# Klok.net
KiCad netlist of a schematic drawn in Altium Designer
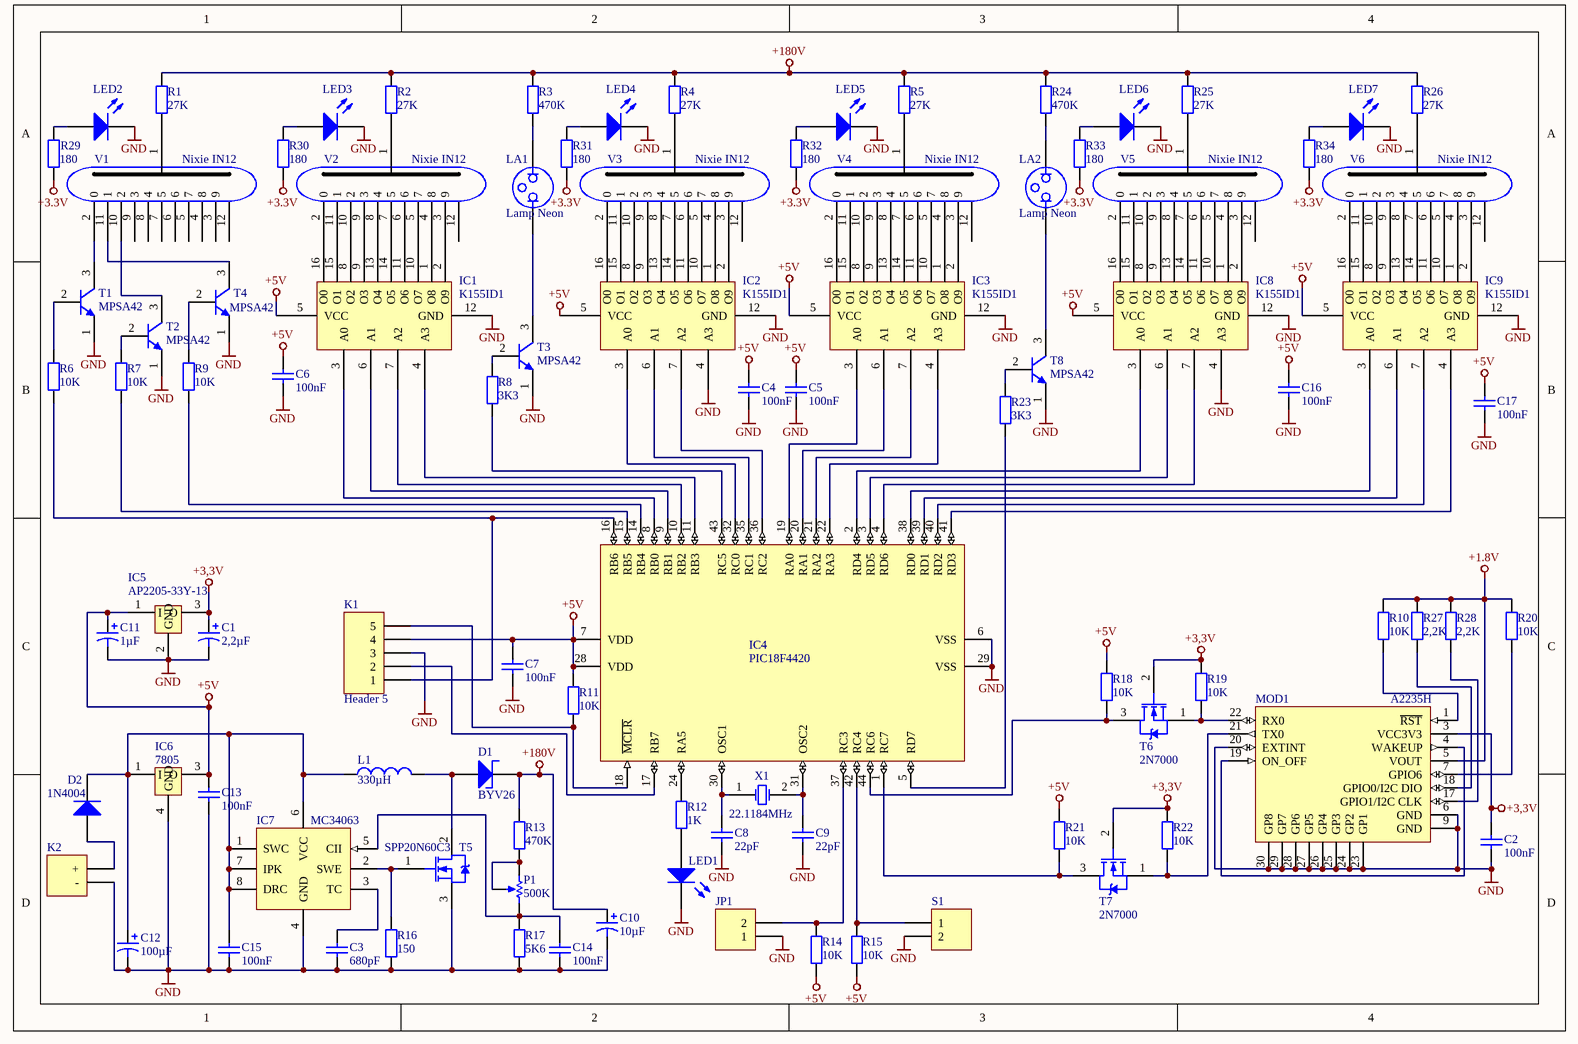
[diagram p0: Klok.SchDoc]

(export (version "E")
  (design (tool "Eeschema 10.0.6"))
  (components
    (comp (ref "C1")
      (value "2,2µF")
      (footprint "ELCO2.2")
      (description "Polarized Capacitor (Radial)")
      (fields (field (name "Comment") "Cap Pol1") (field (name "PUBLISHER") "Altium Limited"))
      (libsource (lib "Miscellaneous Devices") (part "Cap Pol1"))
    )
    (comp (ref "C2")
      (value "100nF")
      (footprint "1206_Capacitor")
      (description "Capacitor")
      (fields (field (name "Comment") "Cap") (field (name "PUBLISHER") "Altium Limited"))
      (libsource (lib "Miscellaneous Devices") (part "Cap"))
    )
    (comp (ref "C3")
      (value "680pF")
      (footprint "1206_Capacitor")
      (description "Capacitor")
      (fields (field (name "Comment") "Cap") (field (name "PUBLISHER") "Altium Limited"))
      (libsource (lib "Miscellaneous Devices") (part "Cap"))
    )
    (comp (ref "C4")
      (value "100nF")
      (footprint "1206_Capacitor")
      (description "Capacitor")
      (fields (field (name "Comment") "Cap") (field (name "PUBLISHER") "Altium Limited"))
      (libsource (lib "Miscellaneous Devices") (part "Cap"))
    )
    (comp (ref "C5")
      (value "100nF")
      (footprint "1206_Capacitor")
      (description "Capacitor")
      (fields (field (name "Comment") "Cap") (field (name "PUBLISHER") "Altium Limited"))
      (libsource (lib "Miscellaneous Devices") (part "Cap"))
    )
    (comp (ref "C6")
      (value "100nF")
      (footprint "1206_Capacitor")
      (description "Capacitor")
      (fields (field (name "Comment") "Cap") (field (name "PUBLISHER") "Altium Limited"))
      (libsource (lib "Miscellaneous Devices") (part "Cap"))
    )
    (comp (ref "C7")
      (value "100nF")
      (footprint "1206_Capacitor")
      (description "Capacitor")
      (fields (field (name "Comment") "Cap") (field (name "PUBLISHER") "Altium Limited"))
      (libsource (lib "Miscellaneous Devices") (part "Cap"))
    )
    (comp (ref "C8")
      (value "22pF")
      (footprint "1206_Capacitor")
      (description "Capacitor")
      (fields (field (name "Comment") "Cap") (field (name "PUBLISHER") "Altium Limited"))
      (libsource (lib "Miscellaneous Devices") (part "Cap"))
    )
    (comp (ref "C9")
      (value "22pF")
      (footprint "1206_Capacitor")
      (description "Capacitor")
      (fields (field (name "Comment") "Cap") (field (name "PUBLISHER") "Altium Limited"))
      (libsource (lib "Miscellaneous Devices") (part "Cap"))
    )
    (comp (ref "C10")
      (value "10µF")
      (footprint "ELCO10")
      (description "Polarized Capacitor (Radial)")
      (fields (field (name "Comment") "Cap Pol1") (field (name "PUBLISHER") "Altium Limited"))
      (libsource (lib "Miscellaneous Devices") (part "Cap Pol1"))
    )
    (comp (ref "C11")
      (value "1µF")
      (footprint "ELCO100")
      (description "Polarized Capacitor (Radial)")
      (fields (field (name "Comment") "Cap Pol1") (field (name "PUBLISHER") "Altium Limited"))
      (libsource (lib "Miscellaneous Devices") (part "Cap Pol1"))
    )
    (comp (ref "C12")
      (value "100µF")
      (footprint "ELCO100")
      (description "Polarized Capacitor (Radial)")
      (fields (field (name "Comment") "Cap Pol1") (field (name "PUBLISHER") "Altium Limited"))
      (libsource (lib "Miscellaneous Devices") (part "Cap Pol1"))
    )
    (comp (ref "C13")
      (value "100nF")
      (footprint "1206_Capacitor")
      (description "Capacitor")
      (fields (field (name "Comment") "Cap") (field (name "PUBLISHER") "Altium Limited"))
      (libsource (lib "Miscellaneous Devices") (part "Cap"))
    )
    (comp (ref "C14")
      (value "100nF")
      (footprint "1206_Capacitor")
      (description "Capacitor")
      (fields (field (name "Comment") "Cap") (field (name "PUBLISHER") "Altium Limited"))
      (libsource (lib "Miscellaneous Devices") (part "Cap"))
    )
    (comp (ref "C15")
      (value "100nF")
      (footprint "1206_Capacitor")
      (description "Capacitor")
      (fields (field (name "Comment") "Cap") (field (name "PUBLISHER") "Altium Limited"))
      (libsource (lib "Miscellaneous Devices") (part "Cap"))
    )
    (comp (ref "C16")
      (value "100nF")
      (footprint "1206_Capacitor")
      (description "Capacitor")
      (fields (field (name "Comment") "Cap") (field (name "PUBLISHER") "Altium Limited"))
      (libsource (lib "Miscellaneous Devices") (part "Cap"))
    )
    (comp (ref "C17")
      (value "100nF")
      (footprint "1206_Capacitor")
      (description "Capacitor")
      (fields (field (name "Comment") "Cap") (field (name "PUBLISHER") "Altium Limited"))
      (libsource (lib "Miscellaneous Devices") (part "Cap"))
    )
    (comp (ref "D1") (value "BYV26") (footprint "Through_Hole") (libsource (lib "Klok") (part "BYV26")))
    (comp (ref "D2")
      (value "1N4004")
      (footprint "DO-41")
      (description "1 Amp General Purpose Rectifier")
      (fields (field (name "PUBLISHER") "Altium Limited"))
      (libsource (lib "Miscellaneous Devices") (part "Diode 1N4004"))
    )
    (comp (ref "IC1") (value "K155ID1") (footprint "K155ID1") (libsource (lib "Klok") (part "K155ID1")))
    (comp (ref "IC2") (value "K155ID1") (footprint "K155ID1") (libsource (lib "Klok") (part "K155ID1")))
    (comp (ref "IC3") (value "K155ID1") (footprint "K155ID1") (libsource (lib "Klok") (part "K155ID1")))
    (comp (ref "IC4")
      (value "PIC18F4420")
      (footprint "PIC18F4420")
      (libsource (lib "Klok") (part "PIC18F4420"))
    )
    (comp (ref "IC5")
      (value "AP2205-33Y-13")
      (footprint "AP2205-33Y-13")
      (libsource (lib "Klok") (part "AP2205-33Y-13"))
    )
    (comp (ref "IC6") (value "7805") (footprint "7805") (libsource (lib "Klok") (part "7805")))
    (comp (ref "IC7") (value "MC34063") (footprint "MC34063") (libsource (lib "Klok") (part "MC34063")))
    (comp (ref "IC8") (value "K155ID1") (footprint "K155ID1") (libsource (lib "Klok") (part "K155ID1")))
    (comp (ref "IC9") (value "K155ID1") (footprint "K155ID1") (libsource (lib "Klok") (part "K155ID1")))
    (comp (ref "JP1")
      (value "Header 2")
      (footprint "HDR1X2")
      (description "Header, 2-Pin")
      (fields (field (name "PUBLISHER") "Altium Limited"))
      (libsource (lib "Miscellaneous Connectors") (part "Header 2"))
    )
    (comp (ref "K1")
      (value "Header 5")
      (footprint "HDR1X5")
      (description "Header, 5-Pin")
      (fields (field (name "PUBLISHER") "Altium Limited"))
      (libsource (lib "Miscellaneous Connectors") (part "Header 5"))
    )
    (comp (ref "K2")
      (value "Kroonsteen")
      (footprint "KROONSTEEN")
      (description "Header, 2-Pin")
      (fields (field (name "PUBLISHER") "Altium Limited"))
      (libsource (lib "") (part "Header 2_1"))
    )
    (comp (ref "L1")
      (value "330µH")
      (footprint "Inductor")
      (description "Inductor")
      (fields (field (name "PUBLISHER") "Altium Limited"))
      (libsource (lib "Miscellaneous Devices") (part "Inductor"))
    )
    (comp (ref "LA1")
      (value "Lamp Neon")
      (footprint "Neon_Lamp")
      (description "Neon Lamp")
      (fields (field (name "PUBLISHER") "Altium Limited"))
      (libsource (lib "Miscellaneous Devices") (part "Lamp Neon"))
    )
    (comp (ref "LA2")
      (value "Lamp Neon")
      (footprint "Neon_Lamp")
      (description "Neon Lamp")
      (fields (field (name "PUBLISHER") "Altium Limited"))
      (libsource (lib "Miscellaneous Devices") (part "Lamp Neon"))
    )
    (comp (ref "LED1")
      (value "LED0")
      (footprint "1206_LED")
      (description "Typical INFRARED GaAs LED")
      (fields (field (name "PUBLISHER") "Altium Limited"))
      (libsource (lib "Miscellaneous Devices") (part "LED0"))
    )
    (comp (ref "LED2")
      (value "LED0")
      (footprint "1206_LED")
      (description "Typical INFRARED GaAs LED")
      (fields (field (name "PUBLISHER") "Altium Limited"))
      (libsource (lib "Miscellaneous Devices") (part "LED0"))
    )
    (comp (ref "LED3")
      (value "LED0")
      (footprint "1206_LED")
      (description "Typical INFRARED GaAs LED")
      (fields (field (name "PUBLISHER") "Altium Limited"))
      (libsource (lib "Miscellaneous Devices") (part "LED0"))
    )
    (comp (ref "LED4")
      (value "LED0")
      (footprint "1206_LED")
      (description "Typical INFRARED GaAs LED")
      (fields (field (name "PUBLISHER") "Altium Limited"))
      (libsource (lib "Miscellaneous Devices") (part "LED0"))
    )
    (comp (ref "LED5")
      (value "LED0")
      (footprint "1206_LED")
      (description "Typical INFRARED GaAs LED")
      (fields (field (name "PUBLISHER") "Altium Limited"))
      (libsource (lib "Miscellaneous Devices") (part "LED0"))
    )
    (comp (ref "LED6")
      (value "LED0")
      (footprint "1206_LED")
      (description "Typical INFRARED GaAs LED")
      (fields (field (name "PUBLISHER") "Altium Limited"))
      (libsource (lib "Miscellaneous Devices") (part "LED0"))
    )
    (comp (ref "LED7")
      (value "LED0")
      (footprint "1206_LED")
      (description "Typical INFRARED GaAs LED")
      (fields (field (name "PUBLISHER") "Altium Limited"))
      (libsource (lib "Miscellaneous Devices") (part "LED0"))
    )
    (comp (ref "MOD1") (value "A2235H") (footprint "A2235H") (libsource (lib "Klok") (part "A2235H")))
    (comp (ref "P1")
      (value "500K")
      (footprint "Pot")
      (description "Potentiometer")
      (fields (field (name "Comment") "RPot") (field (name "PUBLISHER") "Altium Limited"))
      (libsource (lib "Miscellaneous Devices") (part "RPot"))
    )
    (comp (ref "R1")
      (value "27K")
      (footprint "1206_Resistor")
      (description "Resistor")
      (fields (field (name "Comment") "Res2") (field (name "PUBLISHER") "Altium Limited"))
      (libsource (lib "Miscellaneous Devices") (part "Res2"))
    )
    (comp (ref "R2")
      (value "27K")
      (footprint "1206_Resistor")
      (description "Resistor")
      (fields (field (name "Comment") "Res2") (field (name "PUBLISHER") "Altium Limited"))
      (libsource (lib "Miscellaneous Devices") (part "Res2"))
    )
    (comp (ref "R3")
      (value "470K")
      (footprint "1206_Resistor")
      (description "Resistor")
      (fields (field (name "Comment") "Res2") (field (name "PUBLISHER") "Altium Limited"))
      (libsource (lib "Miscellaneous Devices") (part "Res2"))
    )
    (comp (ref "R4")
      (value "27K")
      (footprint "1206_Resistor")
      (description "Resistor")
      (fields (field (name "Comment") "Res2") (field (name "PUBLISHER") "Altium Limited"))
      (libsource (lib "Miscellaneous Devices") (part "Res2"))
    )
    (comp (ref "R5")
      (value "27K")
      (footprint "1206_Resistor")
      (description "Resistor")
      (fields (field (name "Comment") "Res2") (field (name "PUBLISHER") "Altium Limited"))
      (libsource (lib "Miscellaneous Devices") (part "Res2"))
    )
    (comp (ref "R6")
      (value "10K")
      (footprint "1206_Resistor")
      (description "Resistor")
      (fields (field (name "Comment") "Res2") (field (name "PUBLISHER") "Altium Limited"))
      (libsource (lib "Miscellaneous Devices") (part "Res2"))
    )
    (comp (ref "R7")
      (value "10K")
      (footprint "1206_Resistor")
      (description "Resistor")
      (fields (field (name "Comment") "Res2") (field (name "PUBLISHER") "Altium Limited"))
      (libsource (lib "Miscellaneous Devices") (part "Res2"))
    )
    (comp (ref "R8")
      (value "3K3")
      (footprint "1206_Resistor")
      (description "Resistor")
      (fields (field (name "Comment") "Res2") (field (name "PUBLISHER") "Altium Limited"))
      (libsource (lib "Miscellaneous Devices") (part "Res2"))
    )
    (comp (ref "R9")
      (value "10K")
      (footprint "1206_Resistor")
      (description "Resistor")
      (fields (field (name "Comment") "Res2") (field (name "PUBLISHER") "Altium Limited"))
      (libsource (lib "Miscellaneous Devices") (part "Res2"))
    )
    (comp (ref "R10")
      (value "10K")
      (footprint "1206_Resistor")
      (description "Resistor")
      (fields (field (name "Comment") "Res2") (field (name "PUBLISHER") "Altium Limited"))
      (libsource (lib "Miscellaneous Devices") (part "Res2"))
    )
    (comp (ref "R11")
      (value "10K")
      (footprint "1206_Resistor")
      (description "Resistor")
      (fields (field (name "Comment") "Res2") (field (name "PUBLISHER") "Altium Limited"))
      (libsource (lib "Miscellaneous Devices") (part "Res2"))
    )
    (comp (ref "R12")
      (value "1K")
      (footprint "1206_Resistor")
      (description "Resistor")
      (fields (field (name "Comment") "Res2") (field (name "PUBLISHER") "Altium Limited"))
      (libsource (lib "Miscellaneous Devices") (part "Res2"))
    )
    (comp (ref "R13")
      (value "470K")
      (footprint "1206_Resistor")
      (description "Resistor")
      (fields (field (name "Comment") "Res2") (field (name "PUBLISHER") "Altium Limited"))
      (libsource (lib "Miscellaneous Devices") (part "Res2"))
    )
    (comp (ref "R14")
      (value "10K")
      (footprint "1206_Resistor")
      (description "Resistor")
      (fields (field (name "Comment") "Res2") (field (name "PUBLISHER") "Altium Limited"))
      (libsource (lib "Miscellaneous Devices") (part "Res2"))
    )
    (comp (ref "R15")
      (value "10K")
      (footprint "1206_Resistor")
      (description "Resistor")
      (fields (field (name "Comment") "Res2") (field (name "PUBLISHER") "Altium Limited"))
      (libsource (lib "Miscellaneous Devices") (part "Res2"))
    )
    (comp (ref "R16")
      (value "150")
      (footprint "1206_Resistor")
      (description "Resistor")
      (fields (field (name "Comment") "Res2") (field (name "PUBLISHER") "Altium Limited"))
      (libsource (lib "Miscellaneous Devices") (part "Res2"))
    )
    (comp (ref "R17")
      (value "5K6")
      (footprint "1206_Resistor")
      (description "Resistor")
      (fields (field (name "Comment") "Res2") (field (name "PUBLISHER") "Altium Limited"))
      (libsource (lib "Miscellaneous Devices") (part "Res2"))
    )
    (comp (ref "R18")
      (value "10K")
      (footprint "1206_Resistor")
      (description "Resistor")
      (fields (field (name "Comment") "Res2") (field (name "PUBLISHER") "Altium Limited"))
      (libsource (lib "Miscellaneous Devices") (part "Res2"))
    )
    (comp (ref "R19")
      (value "10K")
      (footprint "1206_Resistor")
      (description "Resistor")
      (fields (field (name "Comment") "Res2") (field (name "PUBLISHER") "Altium Limited"))
      (libsource (lib "Miscellaneous Devices") (part "Res2"))
    )
    (comp (ref "R20")
      (value "10K")
      (footprint "1206_Resistor")
      (description "Resistor")
      (fields (field (name "Comment") "Res2") (field (name "PUBLISHER") "Altium Limited"))
      (libsource (lib "Miscellaneous Devices") (part "Res2"))
    )
    (comp (ref "R21")
      (value "10K")
      (footprint "1206_Resistor")
      (description "Resistor")
      (fields (field (name "Comment") "Res2") (field (name "PUBLISHER") "Altium Limited"))
      (libsource (lib "Miscellaneous Devices") (part "Res2"))
    )
    (comp (ref "R22")
      (value "10K")
      (footprint "1206_Resistor")
      (description "Resistor")
      (fields (field (name "Comment") "Res2") (field (name "PUBLISHER") "Altium Limited"))
      (libsource (lib "Miscellaneous Devices") (part "Res2"))
    )
    (comp (ref "R23")
      (value "3K3")
      (footprint "1206_Resistor")
      (description "Resistor")
      (fields (field (name "Comment") "Res2") (field (name "PUBLISHER") "Altium Limited"))
      (libsource (lib "Miscellaneous Devices") (part "Res2"))
    )
    (comp (ref "R24")
      (value "470K")
      (footprint "1206_Resistor")
      (description "Resistor")
      (fields (field (name "Comment") "Res2") (field (name "PUBLISHER") "Altium Limited"))
      (libsource (lib "Miscellaneous Devices") (part "Res2"))
    )
    (comp (ref "R25")
      (value "27K")
      (footprint "1206_Resistor")
      (description "Resistor")
      (fields (field (name "Comment") "Res2") (field (name "PUBLISHER") "Altium Limited"))
      (libsource (lib "Miscellaneous Devices") (part "Res2"))
    )
    (comp (ref "R26")
      (value "27K")
      (footprint "1206_Resistor")
      (description "Resistor")
      (fields (field (name "Comment") "Res2") (field (name "PUBLISHER") "Altium Limited"))
      (libsource (lib "Miscellaneous Devices") (part "Res2"))
    )
    (comp (ref "R27")
      (value "2,2K")
      (footprint "1206_Resistor")
      (description "Resistor")
      (fields (field (name "Comment") "Res2") (field (name "PUBLISHER") "Altium Limited"))
      (libsource (lib "Miscellaneous Devices") (part "Res2"))
    )
    (comp (ref "R28")
      (value "2,2K")
      (footprint "1206_Resistor")
      (description "Resistor")
      (fields (field (name "Comment") "Res2") (field (name "PUBLISHER") "Altium Limited"))
      (libsource (lib "Miscellaneous Devices") (part "Res2"))
    )
    (comp (ref "R29")
      (value "180")
      (footprint "1206_Resistor")
      (description "Resistor")
      (fields (field (name "Comment") "Res2") (field (name "PUBLISHER") "Altium Limited"))
      (libsource (lib "Miscellaneous Devices") (part "Res2"))
    )
    (comp (ref "R30")
      (value "180")
      (footprint "1206_Resistor")
      (description "Resistor")
      (fields (field (name "Comment") "Res2") (field (name "PUBLISHER") "Altium Limited"))
      (libsource (lib "Miscellaneous Devices") (part "Res2"))
    )
    (comp (ref "R31")
      (value "180")
      (footprint "1206_Resistor")
      (description "Resistor")
      (fields (field (name "Comment") "Res2") (field (name "PUBLISHER") "Altium Limited"))
      (libsource (lib "Miscellaneous Devices") (part "Res2"))
    )
    (comp (ref "R32")
      (value "180")
      (footprint "1206_Resistor")
      (description "Resistor")
      (fields (field (name "Comment") "Res2") (field (name "PUBLISHER") "Altium Limited"))
      (libsource (lib "Miscellaneous Devices") (part "Res2"))
    )
    (comp (ref "R33")
      (value "180")
      (footprint "1206_Resistor")
      (description "Resistor")
      (fields (field (name "Comment") "Res2") (field (name "PUBLISHER") "Altium Limited"))
      (libsource (lib "Miscellaneous Devices") (part "Res2"))
    )
    (comp (ref "R34")
      (value "180")
      (footprint "1206_Resistor")
      (description "Resistor")
      (fields (field (name "Comment") "Res2") (field (name "PUBLISHER") "Altium Limited"))
      (libsource (lib "Miscellaneous Devices") (part "Res2"))
    )
    (comp (ref "S1")
      (value "Switch")
      (footprint "HDR1X2")
      (description "Header, 2-Pin")
      (fields (field (name "PUBLISHER") "Altium Limited"))
      (libsource (lib "") (part "Header 2_2"))
    )
    (comp (ref "T1") (value "MPSA42") (footprint "MPSA42") (libsource (lib "Klok") (part "MPSA42")))
    (comp (ref "T2") (value "MPSA42") (footprint "MPSA42") (libsource (lib "Klok") (part "MPSA42")))
    (comp (ref "T3") (value "MPSA42") (footprint "MPSA42") (libsource (lib "Klok") (part "MPSA42")))
    (comp (ref "T4") (value "MPSA42") (footprint "MPSA42") (libsource (lib "Klok") (part "MPSA42")))
    (comp (ref "T5")
      (value "SPP20N60C3")
      (footprint "SPP20N60C3")
      (libsource (lib "Klok") (part "SPP20N60C3"))
    )
    (comp (ref "T6") (value "2N7000") (footprint "2N7000") (libsource (lib "Klok") (part "2N7000")))
    (comp (ref "T7") (value "2N7000") (footprint "2N7000") (libsource (lib "Klok") (part "2N7000")))
    (comp (ref "T8") (value "MPSA42") (footprint "MPSA42") (libsource (lib "Klok") (part "MPSA42")))
    (comp (ref "V1")
      (value "Nixie IN12")
      (footprint "Nixie IN12")
      (libsource (lib "Klok") (part "Nixie IN12"))
    )
    (comp (ref "V2")
      (value "Nixie IN12")
      (footprint "Nixie IN12")
      (libsource (lib "Klok") (part "Nixie IN12"))
    )
    (comp (ref "V3")
      (value "Nixie IN12")
      (footprint "Nixie IN12")
      (libsource (lib "Klok") (part "Nixie IN12"))
    )
    (comp (ref "V4")
      (value "Nixie IN12")
      (footprint "Nixie IN12")
      (libsource (lib "Klok") (part "Nixie IN12"))
    )
    (comp (ref "V5")
      (value "Nixie IN12")
      (footprint "Nixie IN12")
      (libsource (lib "Klok") (part "Nixie IN12"))
    )
    (comp (ref "V6")
      (value "Nixie IN12")
      (footprint "Nixie IN12")
      (libsource (lib "Klok") (part "Nixie IN12"))
    )
    (comp (ref "X1")
      (value "22.1184MHz")
      (footprint "XTAL - duplicate")
      (description "Crystal Oscillator")
      (fields (field (name "PUBLISHER") "Altium Limited"))
      (libsource (lib "Miscellaneous Devices") (part "XTAL"))
    )
  )
  (nets
    (net (code "1") (name "+1.8V") (class "Default")
      (node (ref "MOD1") (pin "5") (pinfunction "VOUT_5") (pintype "power_in"))
      (node (ref "R10") (pin "2") (pinfunction "2_2") (pintype "passive"))
      (node (ref "R20") (pin "2") (pinfunction "2_2") (pintype "passive"))
      (node (ref "R27") (pin "2") (pinfunction "2_2") (pintype "passive"))
      (node (ref "R28") (pin "2") (pinfunction "2_2") (pintype "passive"))
    )
    (net (code "2") (name "+3,3V") (class "Default")
      (node (ref "C1") (pin "1") (pinfunction "1_1") (pintype "passive"))
      (node (ref "C2") (pin "2") (pinfunction "2_2") (pintype "passive"))
      (node (ref "IC5") (pin "3") (pinfunction "O_3") (pintype "power_in"))
      (node (ref "MOD1") (pin "3") (pinfunction "VCC3V3_3") (pintype "power_in"))
      (node (ref "R19") (pin "2") (pinfunction "2_2") (pintype "passive"))
      (node (ref "R22") (pin "2") (pinfunction "2_2") (pintype "passive"))
      (node (ref "T6") (pin "2") (pinfunction "G_2") (pintype "passive"))
      (node (ref "T7") (pin "2") (pinfunction "G_2") (pintype "passive"))
    )
    (net (code "3") (name "+3.3V") (class "Default")
      (node (ref "R29") (pin "1") (pinfunction "1_1") (pintype "passive"))
      (node (ref "R30") (pin "1") (pinfunction "1_1") (pintype "passive"))
      (node (ref "R31") (pin "1") (pinfunction "1_1") (pintype "passive"))
      (node (ref "R32") (pin "1") (pinfunction "1_1") (pintype "passive"))
      (node (ref "R33") (pin "1") (pinfunction "1_1") (pintype "passive"))
      (node (ref "R34") (pin "1") (pinfunction "1_1") (pintype "passive"))
    )
    (net (code "4") (name "+5V") (class "Default")
      (node (ref "C11") (pin "1") (pinfunction "1_1") (pintype "passive"))
      (node (ref "C13") (pin "2") (pinfunction "2_2") (pintype "passive"))
      (node (ref "C16") (pin "2") (pinfunction "2_2") (pintype "passive"))
      (node (ref "C17") (pin "2") (pinfunction "2_2") (pintype "passive"))
      (node (ref "C4") (pin "2") (pinfunction "2_2") (pintype "passive"))
      (node (ref "C5") (pin "2") (pinfunction "2_2") (pintype "passive"))
      (node (ref "C6") (pin "2") (pinfunction "2_2") (pintype "passive"))
      (node (ref "C7") (pin "2") (pinfunction "2_2") (pintype "passive"))
      (node (ref "IC1") (pin "5") (pinfunction "VCC_5") (pintype "passive"))
      (node (ref "IC2") (pin "5") (pinfunction "VCC_5") (pintype "passive"))
      (node (ref "IC3") (pin "5") (pinfunction "VCC_5") (pintype "passive"))
      (node (ref "IC4") (pin "28") (pinfunction "VDD_28") (pintype "power_in"))
      (node (ref "IC4") (pin "7") (pinfunction "VDD_7") (pintype "power_in"))
      (node (ref "IC5") (pin "1") (pinfunction "I_1") (pintype "power_in"))
      (node (ref "IC6") (pin "3") (pinfunction "O_3") (pintype "power_in"))
      (node (ref "IC8") (pin "5") (pinfunction "VCC_5") (pintype "passive"))
      (node (ref "IC9") (pin "5") (pinfunction "VCC_5") (pintype "passive"))
      (node (ref "K1") (pin "4") (pinfunction "4_4") (pintype "passive"))
      (node (ref "R11") (pin "2") (pinfunction "2_2") (pintype "passive"))
      (node (ref "R14") (pin "1") (pinfunction "1_1") (pintype "passive"))
      (node (ref "R15") (pin "1") (pinfunction "1_1") (pintype "passive"))
      (node (ref "R18") (pin "2") (pinfunction "2_2") (pintype "passive"))
      (node (ref "R21") (pin "2") (pinfunction "2_2") (pintype "passive"))
    )
    (net (code "5") (name "+180V") (class "Default")
      (node (ref "C10") (pin "1") (pinfunction "1_1") (pintype "passive"))
      (node (ref "D1") (pin "2") (pinfunction "K_2") (pintype "passive"))
      (node (ref "R1") (pin "2") (pinfunction "2_2") (pintype "passive"))
      (node (ref "R13") (pin "2") (pinfunction "2_2") (pintype "passive"))
      (node (ref "R2") (pin "2") (pinfunction "2_2") (pintype "passive"))
      (node (ref "R24") (pin "2") (pinfunction "2_2") (pintype "passive"))
      (node (ref "R25") (pin "2") (pinfunction "2_2") (pintype "passive"))
      (node (ref "R26") (pin "2") (pinfunction "2_2") (pintype "passive"))
      (node (ref "R3") (pin "2") (pinfunction "2_2") (pintype "passive"))
      (node (ref "R4") (pin "2") (pinfunction "2_2") (pintype "passive"))
      (node (ref "R5") (pin "2") (pinfunction "2_2") (pintype "passive"))
    )
    (net (code "6") (name "GND") (class "Default")
      (node (ref "C1") (pin "2") (pinfunction "2_2") (pintype "passive"))
      (node (ref "C10") (pin "2") (pinfunction "2_2") (pintype "passive"))
      (node (ref "C11") (pin "2") (pinfunction "2_2") (pintype "passive"))
      (node (ref "C12") (pin "2") (pinfunction "2_2") (pintype "passive"))
      (node (ref "C13") (pin "1") (pinfunction "1_1") (pintype "passive"))
      (node (ref "C14") (pin "1") (pinfunction "1_1") (pintype "passive"))
      (node (ref "C15") (pin "1") (pinfunction "1_1") (pintype "passive"))
      (node (ref "C16") (pin "1") (pinfunction "1_1") (pintype "passive"))
      (node (ref "C17") (pin "1") (pinfunction "1_1") (pintype "passive"))
      (node (ref "C2") (pin "1") (pinfunction "1_1") (pintype "passive"))
      (node (ref "C3") (pin "1") (pinfunction "1_1") (pintype "passive"))
      (node (ref "C4") (pin "1") (pinfunction "1_1") (pintype "passive"))
      (node (ref "C5") (pin "1") (pinfunction "1_1") (pintype "passive"))
      (node (ref "C6") (pin "1") (pinfunction "1_1") (pintype "passive"))
      (node (ref "C7") (pin "1") (pinfunction "1_1") (pintype "passive"))
      (node (ref "C8") (pin "1") (pinfunction "1_1") (pintype "passive"))
      (node (ref "C9") (pin "1") (pinfunction "1_1") (pintype "passive"))
      (node (ref "IC1") (pin "12") (pinfunction "GND_12") (pintype "passive"))
      (node (ref "IC2") (pin "12") (pinfunction "GND_12") (pintype "passive"))
      (node (ref "IC2") (pin "4") (pinfunction "A3_4") (pintype "passive"))
      (node (ref "IC3") (pin "12") (pinfunction "GND_12") (pintype "passive"))
      (node (ref "IC4") (pin "29") (pinfunction "VSS_29") (pintype "power_in"))
      (node (ref "IC4") (pin "6") (pinfunction "VSS_6") (pintype "power_in"))
      (node (ref "IC5") (pin "2") (pinfunction "GND_2") (pintype "power_in"))
      (node (ref "IC6") (pin "4") (pinfunction "GND_4") (pintype "power_in"))
      (node (ref "IC7") (pin "4") (pinfunction "GND_4") (pintype "power_in"))
      (node (ref "IC8") (pin "12") (pinfunction "GND_12") (pintype "passive"))
      (node (ref "IC8") (pin "4") (pinfunction "A3_4") (pintype "passive"))
      (node (ref "IC9") (pin "12") (pinfunction "GND_12") (pintype "passive"))
      (node (ref "JP1") (pin "1") (pinfunction "1_1") (pintype "passive"))
      (node (ref "K1") (pin "3") (pinfunction "3_3") (pintype "passive"))
      (node (ref "K2") (pin "1") (pinfunction "-_1") (pintype "passive"))
      (node (ref "LED1") (pin "2") (pinfunction "K_2") (pintype "passive"))
      (node (ref "LED2") (pin "2") (pinfunction "K_2") (pintype "passive"))
      (node (ref "LED3") (pin "2") (pinfunction "K_2") (pintype "passive"))
      (node (ref "LED4") (pin "2") (pinfunction "K_2") (pintype "passive"))
      (node (ref "LED5") (pin "2") (pinfunction "K_2") (pintype "passive"))
      (node (ref "LED6") (pin "2") (pinfunction "K_2") (pintype "passive"))
      (node (ref "LED7") (pin "2") (pinfunction "K_2") (pintype "passive"))
      (node (ref "MOD1") (pin "20") (pinfunction "EXTINT_20") (pintype "bidirectional"))
      (node (ref "MOD1") (pin "23") (pinfunction "GP1_23") (pintype "power_in"))
      (node (ref "MOD1") (pin "24") (pinfunction "GP2_24") (pintype "power_in"))
      (node (ref "MOD1") (pin "25") (pinfunction "GP3_25") (pintype "power_in"))
      (node (ref "MOD1") (pin "26") (pinfunction "GP4_26") (pintype "power_in"))
      (node (ref "MOD1") (pin "27") (pinfunction "GP5_27") (pintype "power_in"))
      (node (ref "MOD1") (pin "28") (pinfunction "GP6_28") (pintype "power_in"))
      (node (ref "MOD1") (pin "29") (pinfunction "GP7_29") (pintype "power_in"))
      (node (ref "MOD1") (pin "30") (pinfunction "GP8_30") (pintype "power_in"))
      (node (ref "MOD1") (pin "6") (pinfunction "GND_6") (pintype "power_in"))
      (node (ref "MOD1") (pin "9") (pinfunction "GND_9") (pintype "power_in"))
      (node (ref "R16") (pin "1") (pinfunction "1_1") (pintype "passive"))
      (node (ref "R17") (pin "1") (pinfunction "1_1") (pintype "passive"))
      (node (ref "S1") (pin "2") (pinfunction "2_2") (pintype "passive"))
      (node (ref "T1") (pin "1") (pinfunction "E_1") (pintype "passive"))
      (node (ref "T2") (pin "1") (pinfunction "E_1") (pintype "passive"))
      (node (ref "T3") (pin "1") (pinfunction "E_1") (pintype "passive"))
      (node (ref "T4") (pin "1") (pinfunction "E_1") (pintype "passive"))
      (node (ref "T5") (pin "3") (pinfunction "SOURCE_3") (pintype "passive"))
      (node (ref "T8") (pin "1") (pinfunction "E_1") (pintype "passive"))
    )
    (net (code "7") (name "Net-(D1-A)") (class "Default")
      (node (ref "D1") (pin "1") (pinfunction "A_1") (pintype "passive"))
      (node (ref "L1") (pin "2") (pinfunction "2_2") (pintype "passive"))
      (node (ref "T5") (pin "2") (pinfunction "DRAIN_2") (pintype "passive"))
    )
    (net (code "8") (name "Net-(D2-A)") (class "Default")
      (node (ref "D2") (pin "1") (pinfunction "A_1") (pintype "passive"))
      (node (ref "K2") (pin "2") (pinfunction "+_2") (pintype "passive"))
    )
    (net (code "9") (name "Net-(D2-K)") (class "Default")
      (node (ref "C12") (pin "1") (pinfunction "1_1") (pintype "passive"))
      (node (ref "C15") (pin "2") (pinfunction "2_2") (pintype "passive"))
      (node (ref "D2") (pin "2") (pinfunction "K_2") (pintype "passive"))
      (node (ref "IC6") (pin "1") (pinfunction "I_1") (pintype "power_in"))
      (node (ref "IC7") (pin "1") (pinfunction "SWC_1") (pintype "open_collector"))
      (node (ref "IC7") (pin "6") (pinfunction "VCC_6") (pintype "power_in"))
      (node (ref "IC7") (pin "7") (pinfunction "IPK_7") (pintype "passive"))
      (node (ref "IC7") (pin "8") (pinfunction "DRC_8") (pintype "open_collector"))
      (node (ref "L1") (pin "1") (pinfunction "1_1") (pintype "passive"))
    )
    (net (code "10") (name "Net-(IC1-A0)") (class "Default")
      (node (ref "IC1") (pin "3") (pinfunction "A0_3") (pintype "passive"))
      (node (ref "IC4") (pin "8") (pinfunction "RB0_8") (pintype "bidirectional"))
    )
    (net (code "11") (name "Net-(IC1-A1)") (class "Default")
      (node (ref "IC1") (pin "6") (pinfunction "A1_6") (pintype "passive"))
      (node (ref "IC4") (pin "9") (pinfunction "RB1_9") (pintype "bidirectional"))
    )
    (net (code "12") (name "Net-(IC1-A2)") (class "Default")
      (node (ref "IC1") (pin "7") (pinfunction "A2_7") (pintype "passive"))
      (node (ref "IC4") (pin "10") (pinfunction "RB2_10") (pintype "bidirectional"))
    )
    (net (code "13") (name "Net-(IC1-A3)") (class "Default")
      (node (ref "IC1") (pin "4") (pinfunction "A3_4") (pintype "passive"))
      (node (ref "IC4") (pin "11") (pinfunction "RB3_11") (pintype "bidirectional"))
    )
    (net (code "14") (name "Net-(IC1-O0)") (class "Default")
      (node (ref "IC1") (pin "16") (pinfunction "O0_16") (pintype "passive"))
      (node (ref "V2") (pin "2") (pinfunction "0_2") (pintype "passive"))
    )
    (net (code "15") (name "Net-(IC1-O1)") (class "Default")
      (node (ref "IC1") (pin "15") (pinfunction "O1_15") (pintype "passive"))
      (node (ref "V2") (pin "11") (pinfunction "1_11") (pintype "passive"))
    )
    (net (code "16") (name "Net-(IC1-O2)") (class "Default")
      (node (ref "IC1") (pin "8") (pinfunction "O2_8") (pintype "passive"))
      (node (ref "V2") (pin "10") (pinfunction "2_10") (pintype "passive"))
    )
    (net (code "17") (name "Net-(IC1-O3)") (class "Default")
      (node (ref "IC1") (pin "9") (pinfunction "O3_9") (pintype "passive"))
      (node (ref "V2") (pin "9") (pinfunction "3_9") (pintype "passive"))
    )
    (net (code "18") (name "Net-(IC1-O4)") (class "Default")
      (node (ref "IC1") (pin "13") (pinfunction "O4_13") (pintype "passive"))
      (node (ref "V2") (pin "8") (pinfunction "4_8") (pintype "passive"))
    )
    (net (code "19") (name "Net-(IC1-O5)") (class "Default")
      (node (ref "IC1") (pin "14") (pinfunction "O5_14") (pintype "passive"))
      (node (ref "V2") (pin "7") (pinfunction "5_7") (pintype "passive"))
    )
    (net (code "20") (name "Net-(IC1-O6)") (class "Default")
      (node (ref "IC1") (pin "11") (pinfunction "O6_11") (pintype "passive"))
      (node (ref "V2") (pin "6") (pinfunction "6_6") (pintype "passive"))
    )
    (net (code "21") (name "Net-(IC1-O7)") (class "Default")
      (node (ref "IC1") (pin "10") (pinfunction "O7_10") (pintype "passive"))
      (node (ref "V2") (pin "5") (pinfunction "7_5") (pintype "passive"))
    )
    (net (code "22") (name "Net-(IC1-O8)") (class "Default")
      (node (ref "IC1") (pin "1") (pinfunction "O8_1") (pintype "passive"))
      (node (ref "V2") (pin "4") (pinfunction "8_4") (pintype "passive"))
    )
    (net (code "23") (name "Net-(IC1-O9)") (class "Default")
      (node (ref "IC1") (pin "2") (pinfunction "O9_2") (pintype "passive"))
      (node (ref "V2") (pin "3") (pinfunction "9_3") (pintype "passive"))
    )
    (net (code "24") (name "Net-(IC2-A0)") (class "Default")
      (node (ref "IC2") (pin "3") (pinfunction "A0_3") (pintype "passive"))
      (node (ref "IC4") (pin "32") (pinfunction "RC0_32") (pintype "bidirectional"))
    )
    (net (code "25") (name "Net-(IC2-A1)") (class "Default")
      (node (ref "IC2") (pin "6") (pinfunction "A1_6") (pintype "passive"))
      (node (ref "IC4") (pin "35") (pinfunction "RC1_35") (pintype "bidirectional"))
    )
    (net (code "26") (name "Net-(IC2-A2)") (class "Default")
      (node (ref "IC2") (pin "7") (pinfunction "A2_7") (pintype "passive"))
      (node (ref "IC4") (pin "36") (pinfunction "RC2_36") (pintype "bidirectional"))
    )
    (net (code "27") (name "Net-(IC2-O0)") (class "Default")
      (node (ref "IC2") (pin "16") (pinfunction "O0_16") (pintype "passive"))
      (node (ref "V3") (pin "2") (pinfunction "0_2") (pintype "passive"))
    )
    (net (code "28") (name "Net-(IC2-O1)") (class "Default")
      (node (ref "IC2") (pin "15") (pinfunction "O1_15") (pintype "passive"))
      (node (ref "V3") (pin "11") (pinfunction "1_11") (pintype "passive"))
    )
    (net (code "29") (name "Net-(IC2-O2)") (class "Default")
      (node (ref "IC2") (pin "8") (pinfunction "O2_8") (pintype "passive"))
      (node (ref "V3") (pin "10") (pinfunction "2_10") (pintype "passive"))
    )
    (net (code "30") (name "Net-(IC2-O3)") (class "Default")
      (node (ref "IC2") (pin "9") (pinfunction "O3_9") (pintype "passive"))
      (node (ref "V3") (pin "9") (pinfunction "3_9") (pintype "passive"))
    )
    (net (code "31") (name "Net-(IC2-O4)") (class "Default")
      (node (ref "IC2") (pin "13") (pinfunction "O4_13") (pintype "passive"))
      (node (ref "V3") (pin "8") (pinfunction "4_8") (pintype "passive"))
    )
    (net (code "32") (name "Net-(IC2-O5)") (class "Default")
      (node (ref "IC2") (pin "14") (pinfunction "O5_14") (pintype "passive"))
      (node (ref "V3") (pin "7") (pinfunction "5_7") (pintype "passive"))
    )
    (net (code "33") (name "Net-(IC2-O6)") (class "Default")
      (node (ref "IC2") (pin "11") (pinfunction "O6_11") (pintype "passive"))
      (node (ref "V3") (pin "6") (pinfunction "6_6") (pintype "passive"))
    )
    (net (code "34") (name "Net-(IC2-O7)") (class "Default")
      (node (ref "IC2") (pin "10") (pinfunction "O7_10") (pintype "passive"))
      (node (ref "V3") (pin "5") (pinfunction "7_5") (pintype "passive"))
    )
    (net (code "35") (name "Net-(IC2-O8)") (class "Default")
      (node (ref "IC2") (pin "1") (pinfunction "O8_1") (pintype "passive"))
      (node (ref "V3") (pin "4") (pinfunction "8_4") (pintype "passive"))
    )
    (net (code "36") (name "Net-(IC2-O9)") (class "Default")
      (node (ref "IC2") (pin "2") (pinfunction "O9_2") (pintype "passive"))
      (node (ref "V3") (pin "3") (pinfunction "9_3") (pintype "passive"))
    )
    (net (code "37") (name "Net-(IC3-A0)") (class "Default")
      (node (ref "IC3") (pin "3") (pinfunction "A0_3") (pintype "passive"))
      (node (ref "IC4") (pin "19") (pinfunction "RA0_19") (pintype "bidirectional"))
    )
    (net (code "38") (name "Net-(IC3-A1)") (class "Default")
      (node (ref "IC3") (pin "6") (pinfunction "A1_6") (pintype "passive"))
      (node (ref "IC4") (pin "20") (pinfunction "RA1_20") (pintype "bidirectional"))
    )
    (net (code "39") (name "Net-(IC3-A2)") (class "Default")
      (node (ref "IC3") (pin "7") (pinfunction "A2_7") (pintype "passive"))
      (node (ref "IC4") (pin "21") (pinfunction "RA2_21") (pintype "bidirectional"))
    )
    (net (code "40") (name "Net-(IC3-A3)") (class "Default")
      (node (ref "IC3") (pin "4") (pinfunction "A3_4") (pintype "passive"))
      (node (ref "IC4") (pin "22") (pinfunction "RA3_22") (pintype "bidirectional"))
    )
    (net (code "41") (name "Net-(IC3-O0)") (class "Default")
      (node (ref "IC3") (pin "16") (pinfunction "O0_16") (pintype "passive"))
      (node (ref "V4") (pin "2") (pinfunction "0_2") (pintype "passive"))
    )
    (net (code "42") (name "Net-(IC3-O1)") (class "Default")
      (node (ref "IC3") (pin "15") (pinfunction "O1_15") (pintype "passive"))
      (node (ref "V4") (pin "11") (pinfunction "1_11") (pintype "passive"))
    )
    (net (code "43") (name "Net-(IC3-O2)") (class "Default")
      (node (ref "IC3") (pin "8") (pinfunction "O2_8") (pintype "passive"))
      (node (ref "V4") (pin "10") (pinfunction "2_10") (pintype "passive"))
    )
    (net (code "44") (name "Net-(IC3-O3)") (class "Default")
      (node (ref "IC3") (pin "9") (pinfunction "O3_9") (pintype "passive"))
      (node (ref "V4") (pin "9") (pinfunction "3_9") (pintype "passive"))
    )
    (net (code "45") (name "Net-(IC3-O4)") (class "Default")
      (node (ref "IC3") (pin "13") (pinfunction "O4_13") (pintype "passive"))
      (node (ref "V4") (pin "8") (pinfunction "4_8") (pintype "passive"))
    )
    (net (code "46") (name "Net-(IC3-O5)") (class "Default")
      (node (ref "IC3") (pin "14") (pinfunction "O5_14") (pintype "passive"))
      (node (ref "V4") (pin "7") (pinfunction "5_7") (pintype "passive"))
    )
    (net (code "47") (name "Net-(IC3-O6)") (class "Default")
      (node (ref "IC3") (pin "11") (pinfunction "O6_11") (pintype "passive"))
      (node (ref "V4") (pin "6") (pinfunction "6_6") (pintype "passive"))
    )
    (net (code "48") (name "Net-(IC3-O7)") (class "Default")
      (node (ref "IC3") (pin "10") (pinfunction "O7_10") (pintype "passive"))
      (node (ref "V4") (pin "5") (pinfunction "7_5") (pintype "passive"))
    )
    (net (code "49") (name "Net-(IC3-O8)") (class "Default")
      (node (ref "IC3") (pin "1") (pinfunction "O8_1") (pintype "passive"))
      (node (ref "V4") (pin "4") (pinfunction "8_4") (pintype "passive"))
    )
    (net (code "50") (name "Net-(IC3-O9)") (class "Default")
      (node (ref "IC3") (pin "2") (pinfunction "O9_2") (pintype "passive"))
      (node (ref "V4") (pin "3") (pinfunction "9_3") (pintype "passive"))
    )
    (net (code "51") (name "Net-(IC4-OSC1)") (class "Default")
      (node (ref "C8") (pin "2") (pinfunction "2_2") (pintype "passive"))
      (node (ref "IC4") (pin "30") (pinfunction "OSC1_30") (pintype "bidirectional"))
      (node (ref "X1") (pin "1") (pinfunction "OSC1_1") (pintype "passive"))
    )
    (net (code "52") (name "Net-(IC4-OSC2)") (class "Default")
      (node (ref "C9") (pin "2") (pinfunction "2_2") (pintype "passive"))
      (node (ref "IC4") (pin "31") (pinfunction "OSC2_31") (pintype "bidirectional"))
      (node (ref "X1") (pin "2") (pinfunction "OSC2_2") (pintype "passive"))
    )
    (net (code "53") (name "Net-(IC4-RA5)") (class "Default")
      (node (ref "IC4") (pin "24") (pinfunction "RA5_24") (pintype "bidirectional"))
      (node (ref "R12") (pin "2") (pinfunction "2_2") (pintype "passive"))
    )
    (net (code "54") (name "Net-(IC4-RB4)") (class "Default")
      (node (ref "IC4") (pin "14") (pinfunction "RB4_14") (pintype "bidirectional"))
      (node (ref "R9") (pin "1") (pinfunction "1_1") (pintype "passive"))
    )
    (net (code "55") (name "Net-(IC4-RB5)") (class "Default")
      (node (ref "IC4") (pin "15") (pinfunction "RB5_15") (pintype "bidirectional"))
      (node (ref "R7") (pin "1") (pinfunction "1_1") (pintype "passive"))
    )
    (net (code "56") (name "Net-(IC4-RB6)") (class "Default")
      (node (ref "IC4") (pin "16") (pinfunction "RB6_16") (pintype "bidirectional"))
      (node (ref "K1") (pin "1") (pinfunction "1_1") (pintype "passive"))
      (node (ref "R6") (pin "1") (pinfunction "1_1") (pintype "passive"))
    )
    (net (code "57") (name "Net-(IC4-RB7)") (class "Default")
      (node (ref "IC4") (pin "17") (pinfunction "RB7_17") (pintype "bidirectional"))
      (node (ref "K1") (pin "2") (pinfunction "2_2") (pintype "passive"))
    )
    (net (code "58") (name "Net-(IC4-RC3)") (class "Default")
      (node (ref "IC4") (pin "37") (pinfunction "RC3_37") (pintype "bidirectional"))
      (node (ref "JP1") (pin "2") (pinfunction "2_2") (pintype "passive"))
      (node (ref "R14") (pin "2") (pinfunction "2_2") (pintype "passive"))
    )
    (net (code "59") (name "Net-(IC4-RC4)") (class "Default")
      (node (ref "IC4") (pin "42") (pinfunction "RC4_42") (pintype "bidirectional"))
      (node (ref "R15") (pin "2") (pinfunction "2_2") (pintype "passive"))
      (node (ref "S1") (pin "1") (pinfunction "1_1") (pintype "passive"))
    )
    (net (code "60") (name "Net-(IC4-RC5)") (class "Default")
      (node (ref "IC4") (pin "43") (pinfunction "RC5_43") (pintype "bidirectional"))
      (node (ref "R8") (pin "1") (pinfunction "1_1") (pintype "passive"))
    )
    (net (code "61") (name "Net-(IC4-RC6)") (class "Default")
      (node (ref "IC4") (pin "44") (pinfunction "RC6_44") (pintype "bidirectional"))
      (node (ref "R18") (pin "1") (pinfunction "1_1") (pintype "passive"))
      (node (ref "T6") (pin "3") (pinfunction "D_3") (pintype "passive"))
    )
    (net (code "62") (name "Net-(IC4-RC7)") (class "Default")
      (node (ref "IC4") (pin "1") (pinfunction "RC7_1") (pintype "bidirectional"))
      (node (ref "R21") (pin "1") (pinfunction "1_1") (pintype "passive"))
      (node (ref "T7") (pin "3") (pinfunction "D_3") (pintype "passive"))
    )
    (net (code "63") (name "Net-(IC4-RD0)") (class "Default")
      (node (ref "IC4") (pin "38") (pinfunction "RD0_38") (pintype "bidirectional"))
      (node (ref "IC9") (pin "3") (pinfunction "A0_3") (pintype "passive"))
    )
    (net (code "64") (name "Net-(IC4-RD1)") (class "Default")
      (node (ref "IC4") (pin "39") (pinfunction "RD1_39") (pintype "bidirectional"))
      (node (ref "IC9") (pin "6") (pinfunction "A1_6") (pintype "passive"))
    )
    (net (code "65") (name "Net-(IC4-RD2)") (class "Default")
      (node (ref "IC4") (pin "40") (pinfunction "RD2_40") (pintype "bidirectional"))
      (node (ref "IC9") (pin "7") (pinfunction "A2_7") (pintype "passive"))
    )
    (net (code "66") (name "Net-(IC4-RD3)") (class "Default")
      (node (ref "IC4") (pin "41") (pinfunction "RD3_41") (pintype "bidirectional"))
      (node (ref "IC9") (pin "4") (pinfunction "A3_4") (pintype "passive"))
    )
    (net (code "67") (name "Net-(IC4-RD4)") (class "Default")
      (node (ref "IC4") (pin "2") (pinfunction "RD4_2") (pintype "bidirectional"))
      (node (ref "IC8") (pin "3") (pinfunction "A0_3") (pintype "passive"))
    )
    (net (code "68") (name "Net-(IC4-RD5)") (class "Default")
      (node (ref "IC4") (pin "3") (pinfunction "RD5_3") (pintype "bidirectional"))
      (node (ref "IC8") (pin "6") (pinfunction "A1_6") (pintype "passive"))
    )
    (net (code "69") (name "Net-(IC4-RD6)") (class "Default")
      (node (ref "IC4") (pin "4") (pinfunction "RD6_4") (pintype "bidirectional"))
      (node (ref "IC8") (pin "7") (pinfunction "A2_7") (pintype "passive"))
    )
    (net (code "70") (name "Net-(IC4-RD7)") (class "Default")
      (node (ref "IC4") (pin "5") (pinfunction "RD7_5") (pintype "bidirectional"))
      (node (ref "R23") (pin "1") (pinfunction "1_1") (pintype "passive"))
    )
    (net (code "71") (name "Net-(IC4-~{MCLR})") (class "Default")
      (node (ref "IC4") (pin "18") (pinfunction "~{MCLR}_18") (pintype "input"))
      (node (ref "K1") (pin "5") (pinfunction "5_5") (pintype "passive"))
      (node (ref "R11") (pin "1") (pinfunction "1_1") (pintype "passive"))
    )
    (net (code "72") (name "Net-(IC7-CII)") (class "Default")
      (node (ref "C14") (pin "2") (pinfunction "2_2") (pintype "passive"))
      (node (ref "IC7") (pin "5") (pinfunction "CII_5") (pintype "input"))
      (node (ref "P1") (pin "2") (pinfunction "BOT_2") (pintype "passive"))
      (node (ref "R17") (pin "2") (pinfunction "2_2") (pintype "passive"))
    )
    (net (code "73") (name "Net-(IC7-SWE)") (class "Default")
      (node (ref "IC7") (pin "2") (pinfunction "SWE_2") (pintype "open_emitter"))
      (node (ref "R16") (pin "2") (pinfunction "2_2") (pintype "passive"))
      (node (ref "T5") (pin "1") (pinfunction "GATE_1") (pintype "passive"))
    )
    (net (code "74") (name "Net-(IC7-TC)") (class "Default")
      (node (ref "C3") (pin "2") (pinfunction "2_2") (pintype "passive"))
      (node (ref "IC7") (pin "3") (pinfunction "TC_3") (pintype "passive"))
    )
    (net (code "75") (name "Net-(IC8-O0)") (class "Default")
      (node (ref "IC8") (pin "16") (pinfunction "O0_16") (pintype "passive"))
      (node (ref "V5") (pin "2") (pinfunction "0_2") (pintype "passive"))
    )
    (net (code "76") (name "Net-(IC8-O1)") (class "Default")
      (node (ref "IC8") (pin "15") (pinfunction "O1_15") (pintype "passive"))
      (node (ref "V5") (pin "11") (pinfunction "1_11") (pintype "passive"))
    )
    (net (code "77") (name "Net-(IC8-O2)") (class "Default")
      (node (ref "IC8") (pin "8") (pinfunction "O2_8") (pintype "passive"))
      (node (ref "V5") (pin "10") (pinfunction "2_10") (pintype "passive"))
    )
    (net (code "78") (name "Net-(IC8-O3)") (class "Default")
      (node (ref "IC8") (pin "9") (pinfunction "O3_9") (pintype "passive"))
      (node (ref "V5") (pin "9") (pinfunction "3_9") (pintype "passive"))
    )
    (net (code "79") (name "Net-(IC8-O4)") (class "Default")
      (node (ref "IC8") (pin "13") (pinfunction "O4_13") (pintype "passive"))
      (node (ref "V5") (pin "8") (pinfunction "4_8") (pintype "passive"))
    )
    (net (code "80") (name "Net-(IC8-O5)") (class "Default")
      (node (ref "IC8") (pin "14") (pinfunction "O5_14") (pintype "passive"))
      (node (ref "V5") (pin "7") (pinfunction "5_7") (pintype "passive"))
    )
    (net (code "81") (name "Net-(IC8-O6)") (class "Default")
      (node (ref "IC8") (pin "11") (pinfunction "O6_11") (pintype "passive"))
      (node (ref "V5") (pin "6") (pinfunction "6_6") (pintype "passive"))
    )
    (net (code "82") (name "Net-(IC8-O7)") (class "Default")
      (node (ref "IC8") (pin "10") (pinfunction "O7_10") (pintype "passive"))
      (node (ref "V5") (pin "5") (pinfunction "7_5") (pintype "passive"))
    )
    (net (code "83") (name "Net-(IC8-O8)") (class "Default")
      (node (ref "IC8") (pin "1") (pinfunction "O8_1") (pintype "passive"))
      (node (ref "V5") (pin "4") (pinfunction "8_4") (pintype "passive"))
    )
    (net (code "84") (name "Net-(IC8-O9)") (class "Default")
      (node (ref "IC8") (pin "2") (pinfunction "O9_2") (pintype "passive"))
      (node (ref "V5") (pin "3") (pinfunction "9_3") (pintype "passive"))
    )
    (net (code "85") (name "Net-(IC9-O0)") (class "Default")
      (node (ref "IC9") (pin "16") (pinfunction "O0_16") (pintype "passive"))
      (node (ref "V6") (pin "2") (pinfunction "0_2") (pintype "passive"))
    )
    (net (code "86") (name "Net-(IC9-O1)") (class "Default")
      (node (ref "IC9") (pin "15") (pinfunction "O1_15") (pintype "passive"))
      (node (ref "V6") (pin "11") (pinfunction "1_11") (pintype "passive"))
    )
    (net (code "87") (name "Net-(IC9-O2)") (class "Default")
      (node (ref "IC9") (pin "8") (pinfunction "O2_8") (pintype "passive"))
      (node (ref "V6") (pin "10") (pinfunction "2_10") (pintype "passive"))
    )
    (net (code "88") (name "Net-(IC9-O3)") (class "Default")
      (node (ref "IC9") (pin "9") (pinfunction "O3_9") (pintype "passive"))
      (node (ref "V6") (pin "9") (pinfunction "3_9") (pintype "passive"))
    )
    (net (code "89") (name "Net-(IC9-O4)") (class "Default")
      (node (ref "IC9") (pin "13") (pinfunction "O4_13") (pintype "passive"))
      (node (ref "V6") (pin "8") (pinfunction "4_8") (pintype "passive"))
    )
    (net (code "90") (name "Net-(IC9-O5)") (class "Default")
      (node (ref "IC9") (pin "14") (pinfunction "O5_14") (pintype "passive"))
      (node (ref "V6") (pin "7") (pinfunction "5_7") (pintype "passive"))
    )
    (net (code "91") (name "Net-(IC9-O6)") (class "Default")
      (node (ref "IC9") (pin "11") (pinfunction "O6_11") (pintype "passive"))
      (node (ref "V6") (pin "6") (pinfunction "6_6") (pintype "passive"))
    )
    (net (code "92") (name "Net-(IC9-O7)") (class "Default")
      (node (ref "IC9") (pin "10") (pinfunction "O7_10") (pintype "passive"))
      (node (ref "V6") (pin "5") (pinfunction "7_5") (pintype "passive"))
    )
    (net (code "93") (name "Net-(IC9-O8)") (class "Default")
      (node (ref "IC9") (pin "1") (pinfunction "O8_1") (pintype "passive"))
      (node (ref "V6") (pin "4") (pinfunction "8_4") (pintype "passive"))
    )
    (net (code "94") (name "Net-(IC9-O9)") (class "Default")
      (node (ref "IC9") (pin "2") (pinfunction "O9_2") (pintype "passive"))
      (node (ref "V6") (pin "3") (pinfunction "9_3") (pintype "passive"))
    )
    (net (code "95") (name "Net-(LA1-Pad2)") (class "Default")
      (node (ref "LA1") (pin "2") (pinfunction "2_2") (pintype "passive"))
      (node (ref "R3") (pin "1") (pinfunction "1_1") (pintype "passive"))
    )
    (net (code "96") (name "Net-(LA2-Pad2)") (class "Default")
      (node (ref "LA2") (pin "2") (pinfunction "2_2") (pintype "passive"))
      (node (ref "R24") (pin "1") (pinfunction "1_1") (pintype "passive"))
    )
    (net (code "97") (name "Net-(LED1-A)") (class "Default")
      (node (ref "LED1") (pin "1") (pinfunction "A_1") (pintype "passive"))
      (node (ref "R12") (pin "1") (pinfunction "1_1") (pintype "passive"))
    )
    (net (code "98") (name "Net-(LED2-A)") (class "Default")
      (node (ref "LED2") (pin "1") (pinfunction "A_1") (pintype "passive"))
      (node (ref "R29") (pin "2") (pinfunction "2_2") (pintype "passive"))
    )
    (net (code "99") (name "Net-(LED3-A)") (class "Default")
      (node (ref "LED3") (pin "1") (pinfunction "A_1") (pintype "passive"))
      (node (ref "R30") (pin "2") (pinfunction "2_2") (pintype "passive"))
    )
    (net (code "100") (name "Net-(LED4-A)") (class "Default")
      (node (ref "LED4") (pin "1") (pinfunction "A_1") (pintype "passive"))
      (node (ref "R31") (pin "2") (pinfunction "2_2") (pintype "passive"))
    )
    (net (code "101") (name "Net-(LED5-A)") (class "Default")
      (node (ref "LED5") (pin "1") (pinfunction "A_1") (pintype "passive"))
      (node (ref "R32") (pin "2") (pinfunction "2_2") (pintype "passive"))
    )
    (net (code "102") (name "Net-(LED6-A)") (class "Default")
      (node (ref "LED6") (pin "1") (pinfunction "A_1") (pintype "passive"))
      (node (ref "R33") (pin "2") (pinfunction "2_2") (pintype "passive"))
    )
    (net (code "103") (name "Net-(LED7-A)") (class "Default")
      (node (ref "LED7") (pin "1") (pinfunction "A_1") (pintype "passive"))
      (node (ref "R34") (pin "2") (pinfunction "2_2") (pintype "passive"))
    )
    (net (code "104") (name "Net-(MOD1-GPIO0{slash}I2C_DIO)") (class "Default")
      (node (ref "MOD1") (pin "18") (pinfunction "GPIO0/I2C_DIO_18") (pintype "bidirectional"))
      (node (ref "R27") (pin "1") (pinfunction "1_1") (pintype "passive"))
    )
    (net (code "105") (name "Net-(MOD1-GPIO1{slash}I2C_CLK)") (class "Default")
      (node (ref "MOD1") (pin "17") (pinfunction "GPIO1/I2C_CLK_17") (pintype "bidirectional"))
      (node (ref "R28") (pin "1") (pinfunction "1_1") (pintype "passive"))
    )
    (net (code "106") (name "Net-(MOD1-GPIO6)") (class "Default")
      (node (ref "MOD1") (pin "7") (pinfunction "GPIO6_7") (pintype "bidirectional"))
      (node (ref "R20") (pin "1") (pinfunction "1_1") (pintype "passive"))
    )
    (net (code "107") (name "Net-(MOD1-ON_OFF)") (class "Default")
      (node (ref "MOD1") (pin "19") (pinfunction "ON_OFF_19") (pintype "input"))
      (node (ref "MOD1") (pin "4") (pinfunction "WAKEUP_4") (pintype "output"))
    )
    (net (code "108") (name "Net-(MOD1-RX0)") (class "Default")
      (node (ref "MOD1") (pin "22") (pinfunction "RX0_22") (pintype "bidirectional"))
      (node (ref "R19") (pin "1") (pinfunction "1_1") (pintype "passive"))
      (node (ref "T6") (pin "1") (pinfunction "S_1") (pintype "passive"))
    )
    (net (code "109") (name "Net-(MOD1-TX0)") (class "Default")
      (node (ref "MOD1") (pin "21") (pinfunction "TX0_21") (pintype "output"))
      (node (ref "R22") (pin "1") (pinfunction "1_1") (pintype "passive"))
      (node (ref "T7") (pin "1") (pinfunction "S_1") (pintype "passive"))
    )
    (net (code "110") (name "Net-(MOD1-~{RST})") (class "Default")
      (node (ref "MOD1") (pin "1") (pinfunction "~{RST}_1") (pintype "input"))
      (node (ref "R10") (pin "1") (pinfunction "1_1") (pintype "passive"))
    )
    (net (code "111") (name "Net-(P1-TAP)") (class "Default")
      (node (ref "P1") (pin "1") (pinfunction "TOP_1") (pintype "passive"))
      (node (ref "P1") (pin "3") (pinfunction "TAP_3") (pintype "passive"))
      (node (ref "R13") (pin "1") (pinfunction "1_1") (pintype "passive"))
    )
    (net (code "112") (name "Net-(T1-B)") (class "Default")
      (node (ref "R6") (pin "2") (pinfunction "2_2") (pintype "passive"))
      (node (ref "T1") (pin "2") (pinfunction "B_2") (pintype "passive"))
    )
    (net (code "113") (name "Net-(T1-C)") (class "Default")
      (node (ref "T1") (pin "3") (pinfunction "C_3") (pintype "passive"))
      (node (ref "V1") (pin "2") (pinfunction "0_2") (pintype "passive"))
    )
    (net (code "114") (name "Net-(T2-B)") (class "Default")
      (node (ref "R7") (pin "2") (pinfunction "2_2") (pintype "passive"))
      (node (ref "T2") (pin "2") (pinfunction "B_2") (pintype "passive"))
    )
    (net (code "115") (name "Net-(T2-C)") (class "Default")
      (node (ref "T2") (pin "3") (pinfunction "C_3") (pintype "passive"))
      (node (ref "V1") (pin "10") (pinfunction "2_10") (pintype "passive"))
    )
    (net (code "116") (name "Net-(T3-B)") (class "Default")
      (node (ref "R8") (pin "2") (pinfunction "2_2") (pintype "passive"))
      (node (ref "T3") (pin "2") (pinfunction "B_2") (pintype "passive"))
    )
    (net (code "117") (name "Net-(T3-C)") (class "Default")
      (node (ref "LA1") (pin "1") (pinfunction "1_1") (pintype "passive"))
      (node (ref "T3") (pin "3") (pinfunction "C_3") (pintype "passive"))
    )
    (net (code "118") (name "Net-(T4-B)") (class "Default")
      (node (ref "R9") (pin "2") (pinfunction "2_2") (pintype "passive"))
      (node (ref "T4") (pin "2") (pinfunction "B_2") (pintype "passive"))
    )
    (net (code "119") (name "Net-(T4-C)") (class "Default")
      (node (ref "T4") (pin "3") (pinfunction "C_3") (pintype "passive"))
      (node (ref "V1") (pin "11") (pinfunction "1_11") (pintype "passive"))
    )
    (net (code "120") (name "Net-(T8-B)") (class "Default")
      (node (ref "R23") (pin "2") (pinfunction "2_2") (pintype "passive"))
      (node (ref "T8") (pin "2") (pinfunction "B_2") (pintype "passive"))
    )
    (net (code "121") (name "Net-(T8-C)") (class "Default")
      (node (ref "LA2") (pin "1") (pinfunction "1_1") (pintype "passive"))
      (node (ref "T8") (pin "3") (pinfunction "C_3") (pintype "passive"))
    )
    (net (code "122") (name "Net-(V1-14)") (class "Default")
      (node (ref "R1") (pin "1") (pinfunction "1_1") (pintype "passive"))
      (node (ref "V1") (pin "1") (pinfunction "14_1") (pintype "passive"))
    )
    (net (code "123") (name "Net-(V2-14)") (class "Default")
      (node (ref "R2") (pin "1") (pinfunction "1_1") (pintype "passive"))
      (node (ref "V2") (pin "1") (pinfunction "14_1") (pintype "passive"))
    )
    (net (code "124") (name "Net-(V3-14)") (class "Default")
      (node (ref "R4") (pin "1") (pinfunction "1_1") (pintype "passive"))
      (node (ref "V3") (pin "1") (pinfunction "14_1") (pintype "passive"))
    )
    (net (code "125") (name "Net-(V4-14)") (class "Default")
      (node (ref "R5") (pin "1") (pinfunction "1_1") (pintype "passive"))
      (node (ref "V4") (pin "1") (pinfunction "14_1") (pintype "passive"))
    )
    (net (code "126") (name "Net-(V5-14)") (class "Default")
      (node (ref "R25") (pin "1") (pinfunction "1_1") (pintype "passive"))
      (node (ref "V5") (pin "1") (pinfunction "14_1") (pintype "passive"))
    )
    (net (code "127") (name "Net-(V6-14)") (class "Default")
      (node (ref "R26") (pin "1") (pinfunction "1_1") (pintype "passive"))
      (node (ref "V6") (pin "1") (pinfunction "14_1") (pintype "passive"))
    )
    (net (code "128") (name "unconnected-(V1-3-Pad9)") (class "Default")
      (node (ref "V1") (pin "9") (pinfunction "3_9") (pintype "passive"))
    )
    (net (code "129") (name "unconnected-(V1-4-Pad8)") (class "Default")
      (node (ref "V1") (pin "8") (pinfunction "4_8") (pintype "passive"))
    )
    (net (code "130") (name "unconnected-(V1-5-Pad7)") (class "Default")
      (node (ref "V1") (pin "7") (pinfunction "5_7") (pintype "passive"))
    )
    (net (code "131") (name "unconnected-(V1-7-Pad5)") (class "Default")
      (node (ref "V1") (pin "5") (pinfunction "7_5") (pintype "passive"))
    )
    (net (code "132") (name "unconnected-(V1-8-Pad4)") (class "Default")
      (node (ref "V1") (pin "4") (pinfunction "8_4") (pintype "passive"))
    )
    (net (code "133") (name "unconnected-(V1-9-Pad3)") (class "Default")
      (node (ref "V1") (pin "3") (pinfunction "9_3") (pintype "passive"))
    )
    (net (code "134") (name "unconnected-(V1-25-Pad12)") (class "Default")
      (node (ref "V1") (pin "12") (pinfunction "25_12") (pintype "passive"))
    )
    (net (code "135") (name "unconnected-(V1-Pad6)") (class "Default")
      (node (ref "V1") (pin "6") (pinfunction "6_6") (pintype "passive"))
    )
    (net (code "136") (name "unconnected-(V2-25-Pad12)") (class "Default")
      (node (ref "V2") (pin "12") (pinfunction "25_12") (pintype "passive"))
    )
    (net (code "137") (name "unconnected-(V3-25-Pad12)") (class "Default")
      (node (ref "V3") (pin "12") (pinfunction "25_12") (pintype "passive"))
    )
    (net (code "138") (name "unconnected-(V4-25-Pad12)") (class "Default")
      (node (ref "V4") (pin "12") (pinfunction "25_12") (pintype "passive"))
    )
    (net (code "139") (name "unconnected-(V5-25-Pad12)") (class "Default")
      (node (ref "V5") (pin "12") (pinfunction "25_12") (pintype "passive"))
    )
    (net (code "140") (name "unconnected-(V6-25-Pad12)") (class "Default")
      (node (ref "V6") (pin "12") (pinfunction "25_12") (pintype "passive"))
    )
  )
)
